# CAN_TOF.net
KiCad netlist of a schematic drawn in EAGLE
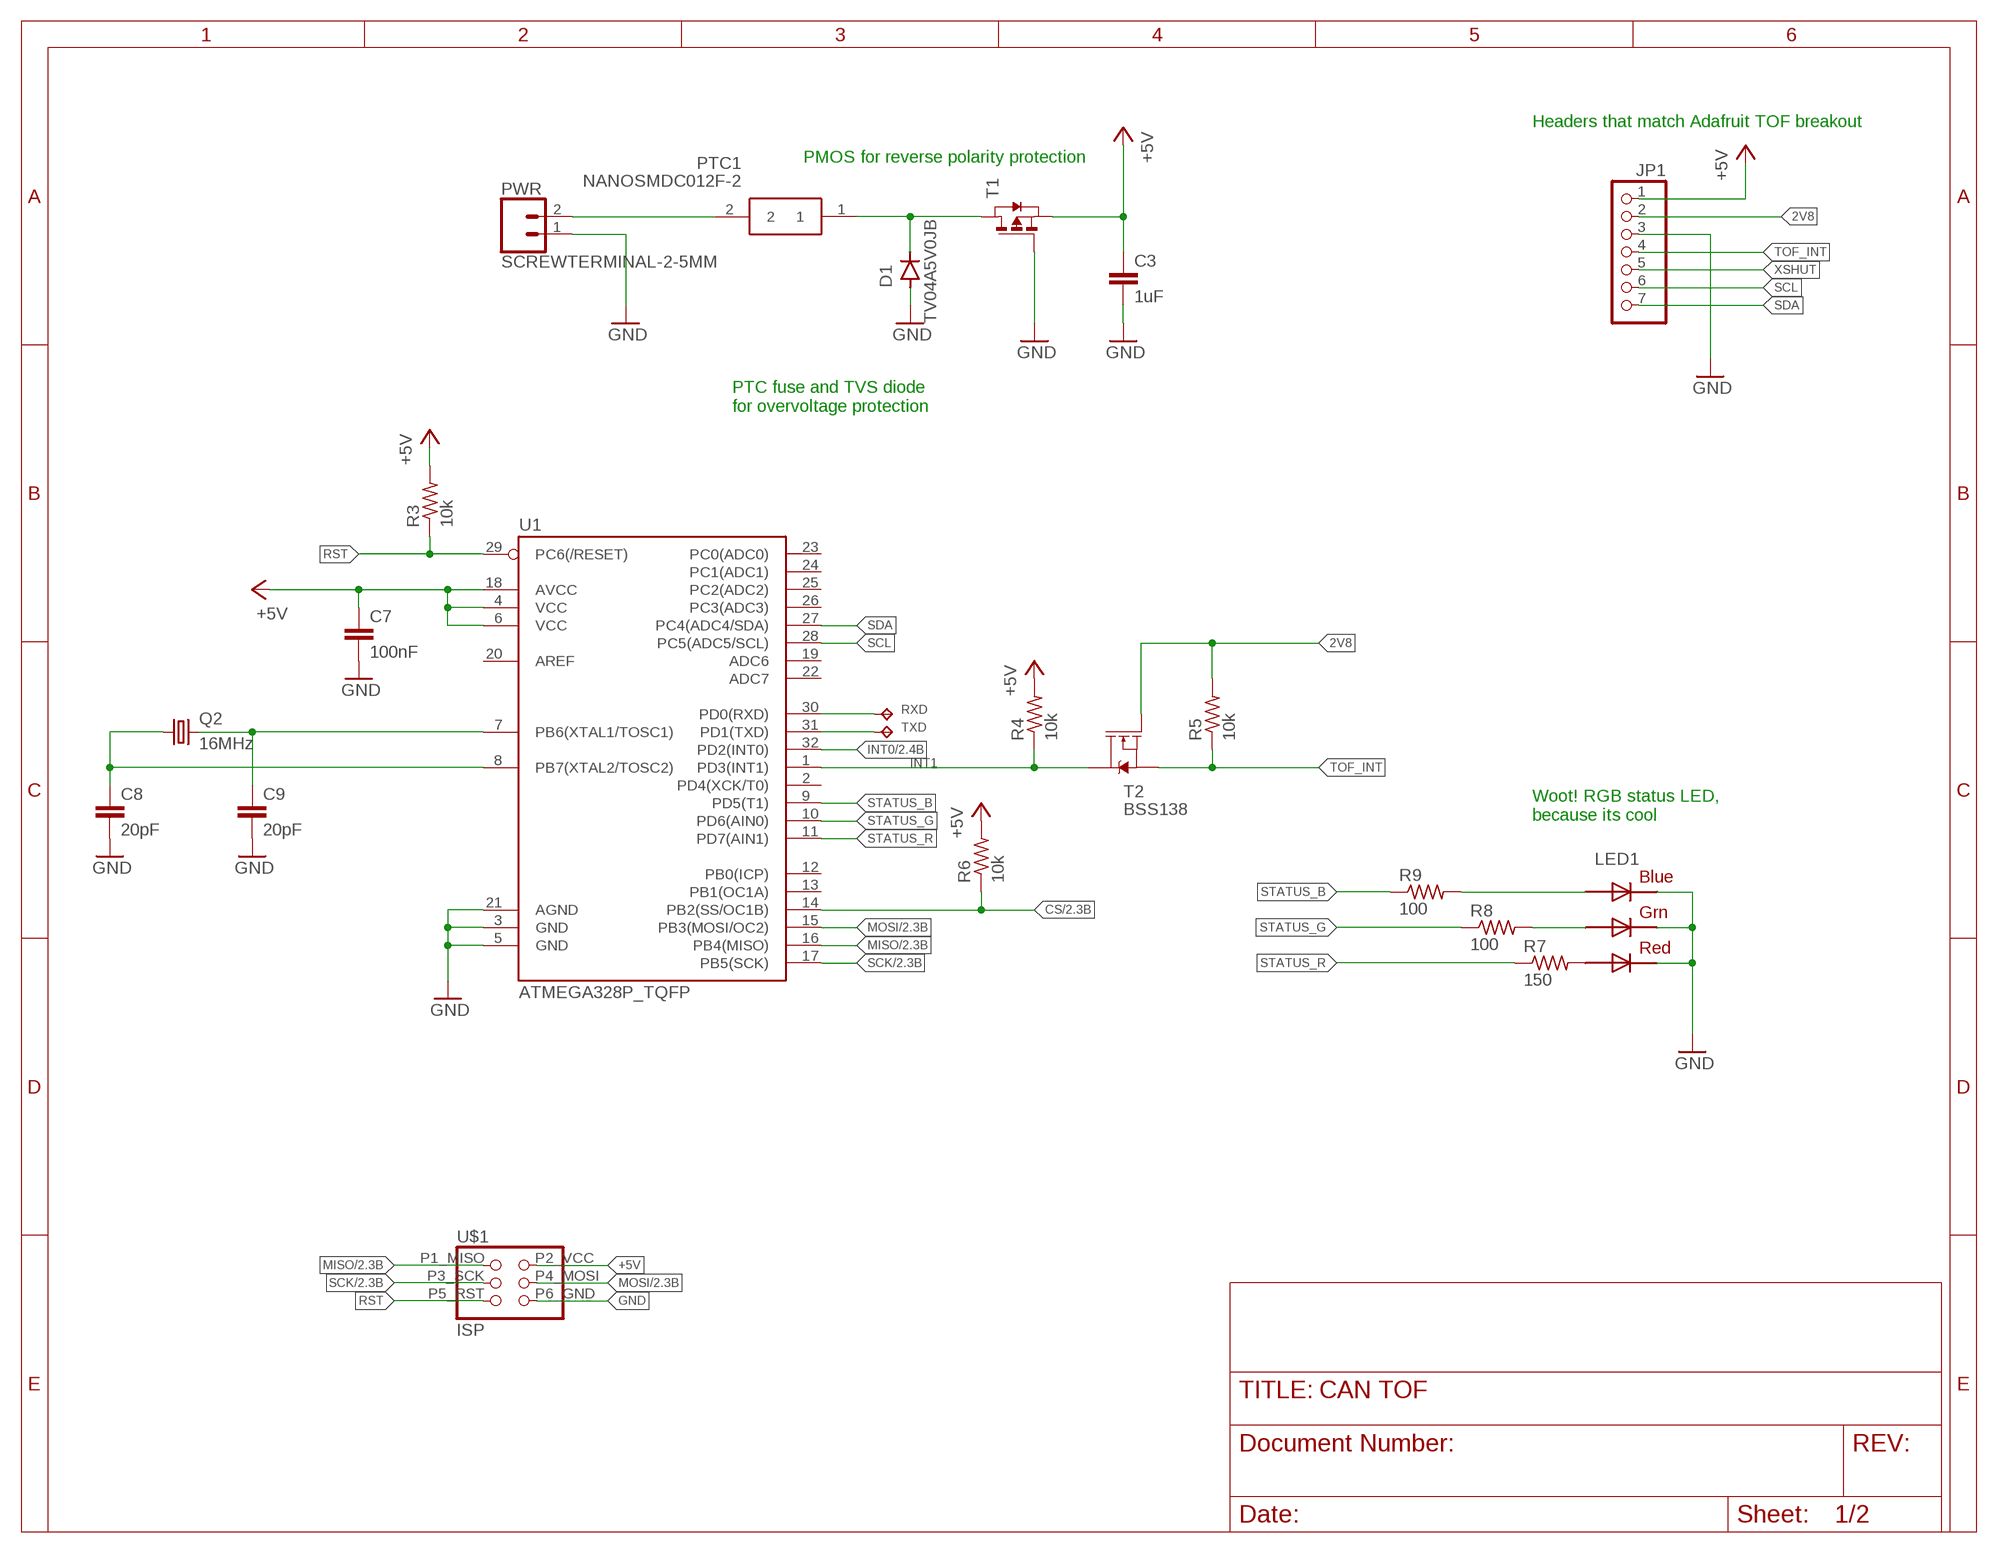
[diagram p0: schematic, sheet 1]
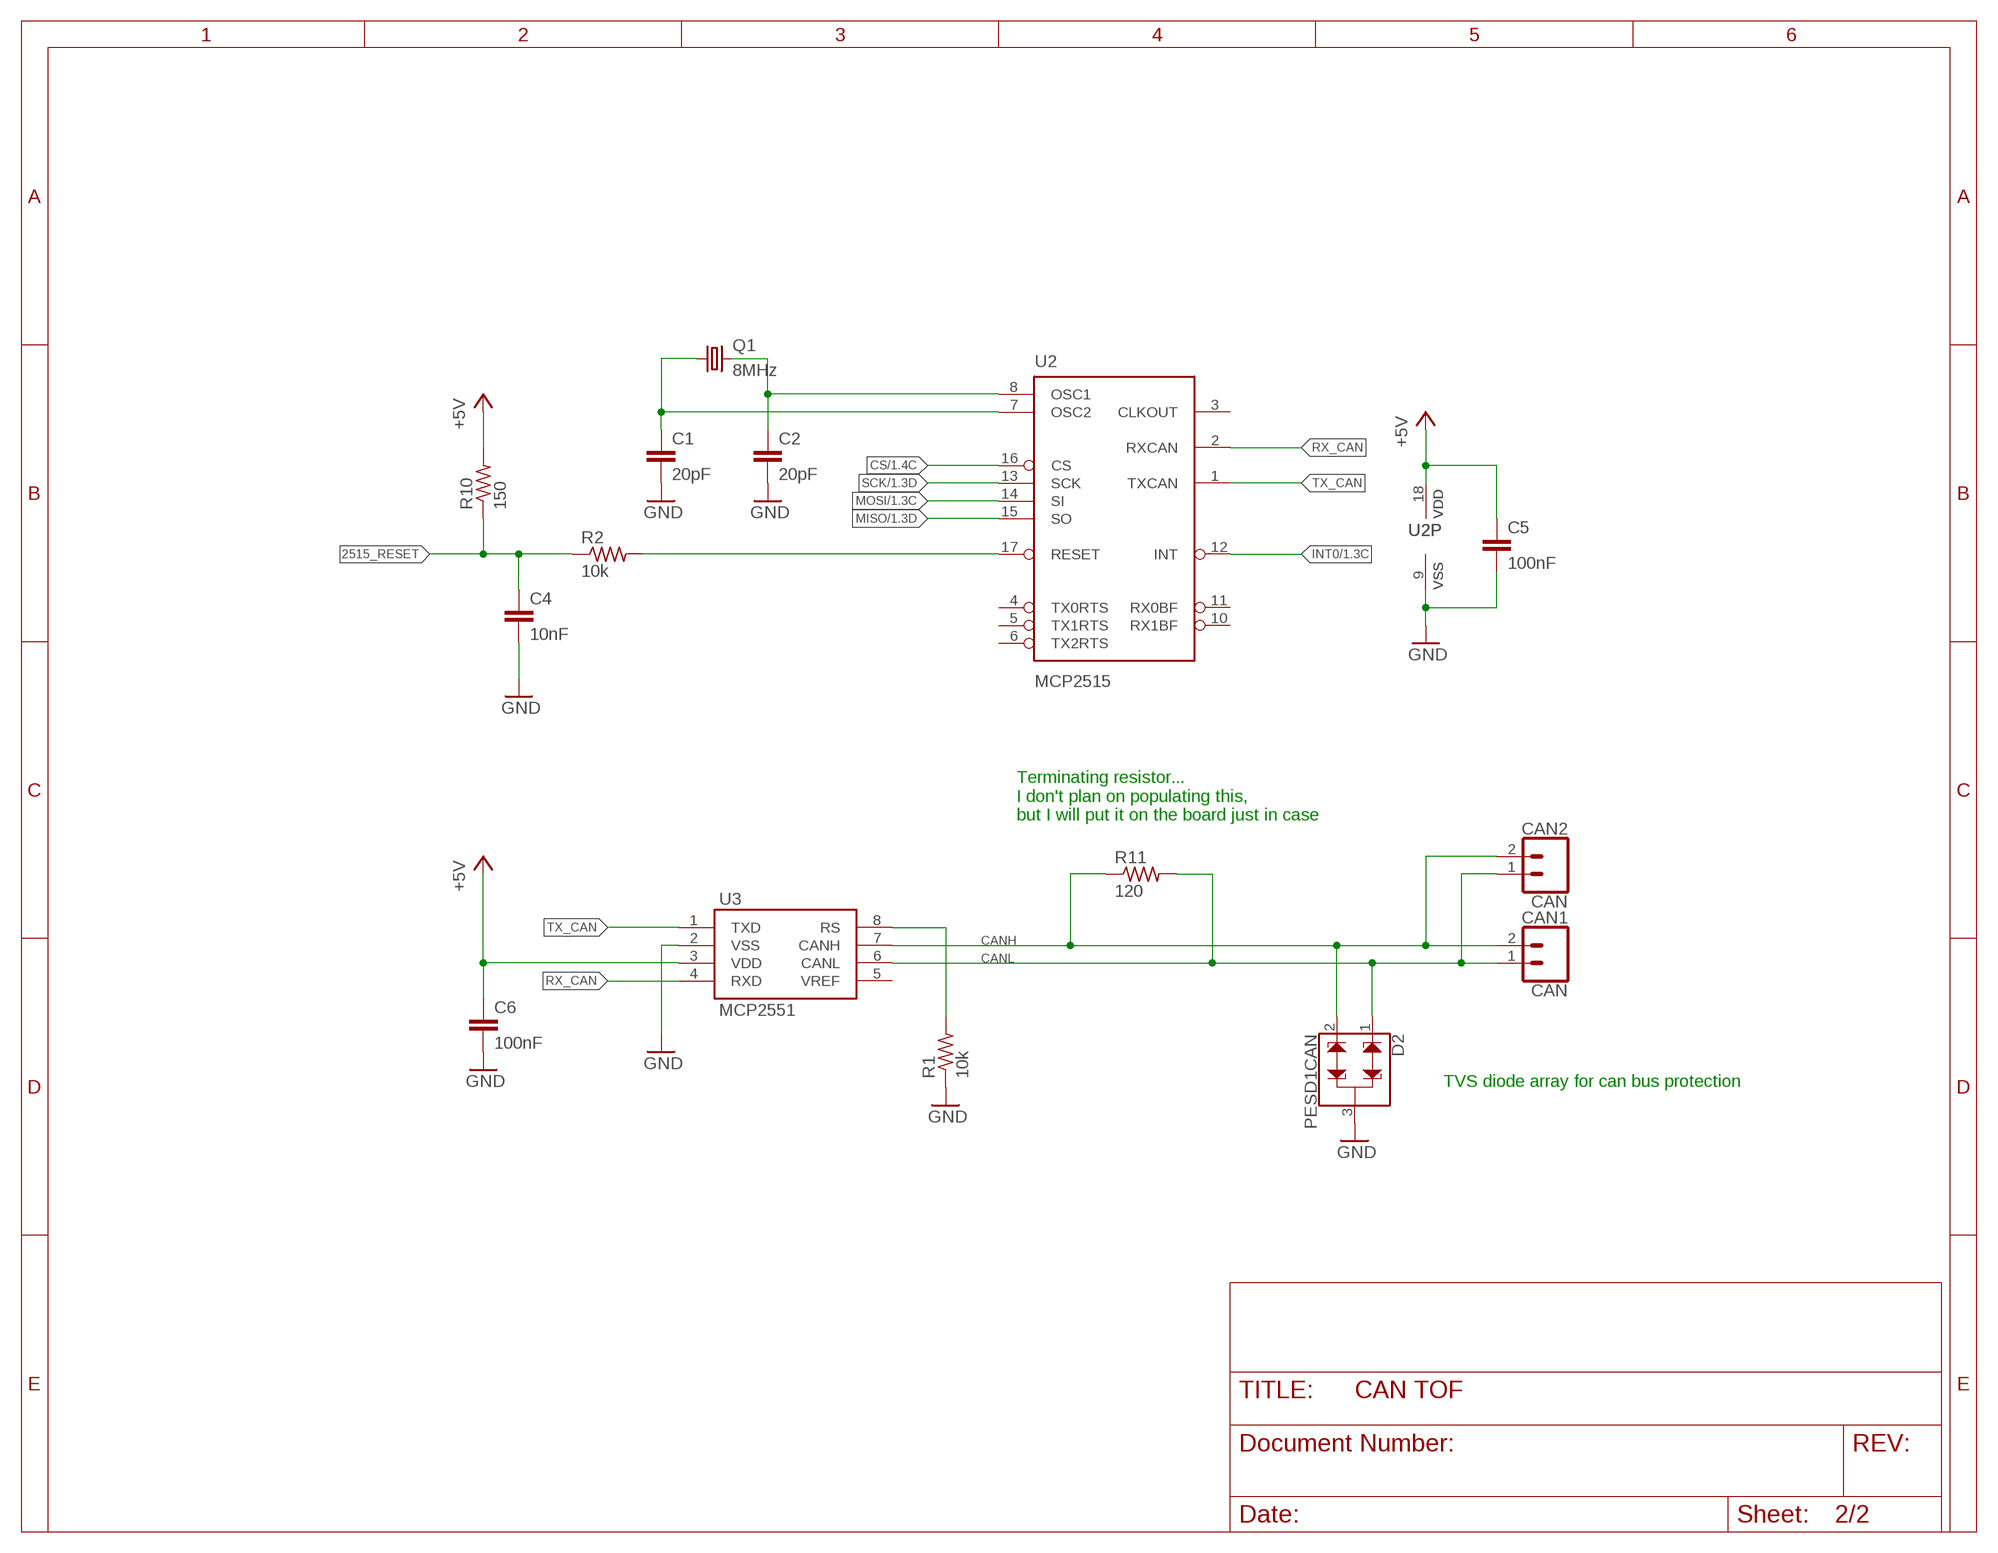
[diagram p1: schematic, sheet 2]

(export (version "E")
  (design (tool "Eeschema 10.0.6"))
  (components
    (comp (ref "C3")
      (value "1uF")
      (footprint "eagle-import:C0805")
      (libsource (lib "eagle-import") (part "C-EUC0805"))
    )
    (comp (ref "C7")
      (value "100nF")
      (footprint "eagle-import:C0402")
      (libsource (lib "eagle-import") (part "C-EUC0402"))
    )
    (comp (ref "C8")
      (value "20pF")
      (footprint "eagle-import:C0402")
      (libsource (lib "eagle-import") (part "C-EUC0402"))
    )
    (comp (ref "C9")
      (value "20pF")
      (footprint "eagle-import:C0402")
      (libsource (lib "eagle-import") (part "C-EUC0402"))
    )
    (comp (ref "D1")
      (value "TV04A5V0JB")
      (footprint "eagle-import:SMA-DO214AC")
      (libsource (lib "eagle-import") (part "GF1"))
    )
    (comp (ref "JP1")
      (value "PINHD-1X7")
      (footprint "eagle-import:1X07")
      (libsource (lib "eagle-import") (part "PINHD-1X7"))
    )
    (comp (ref "LED1")
      (value "RGBLED5050")
      (footprint "eagle-import:RGBLED5050")
      (libsource (lib "eagle-import") (part "RGBLED5050"))
    )
    (comp (ref "PTC1")
      (value "NANOSMDC012F-2")
      (footprint "eagle-import:FUSC3216X100N")
      (fields
        (field (name "MANUFACTURER_PART_NUMBER") "NANOSMDC010F-2")
        (field (name "MOUSER_PART_NUMBER") "650-NANOSMDC010F-2")
      )
      (libsource (lib "eagle-import") (part "NANOSMDC010F-2"))
    )
    (comp (ref "PWR")
      (value "SCREWTERMINAL-2-5MM")
      (footprint "eagle-import:SCREWTERMINAL-5MM-2")
      (libsource (lib "eagle-import") (part "SCREWTERMINAL-2-5MM"))
    )
    (comp (ref "Q2")
      (value "16MHz")
      (footprint "eagle-import:CTS406")
      (libsource (lib "eagle-import") (part "CRYSTALCTS406"))
    )
    (comp (ref "R3")
      (value "10k")
      (footprint "eagle-import:R0805")
      (libsource (lib "eagle-import") (part "R-US_R0805"))
    )
    (comp (ref "R4")
      (value "10k")
      (footprint "eagle-import:R0805")
      (libsource (lib "eagle-import") (part "R-US_R0805"))
    )
    (comp (ref "R5")
      (value "10k")
      (footprint "eagle-import:R0805")
      (libsource (lib "eagle-import") (part "R-US_R0805"))
    )
    (comp (ref "R6")
      (value "10k")
      (footprint "eagle-import:R0805")
      (libsource (lib "eagle-import") (part "R-US_R0805"))
    )
    (comp (ref "R7")
      (value "150")
      (footprint "eagle-import:R0805")
      (libsource (lib "eagle-import") (part "R-US_R0805"))
    )
    (comp (ref "R8")
      (value "100")
      (footprint "eagle-import:R0805")
      (libsource (lib "eagle-import") (part "R-US_R0805"))
    )
    (comp (ref "R9")
      (value "100")
      (footprint "eagle-import:R0805")
      (libsource (lib "eagle-import") (part "R-US_R0805"))
    )
    (comp (ref "RXD")
      (value "TPB1,27")
      (footprint "eagle-import:B1,27")
      (libsource (lib "eagle-import") (part "TPB1,27"))
    )
    (comp (ref "T1")
      (value "PMOSSOT23")
      (footprint "eagle-import:SOT-23")
      (libsource (lib "eagle-import") (part "PMOSSOT23"))
    )
    (comp (ref "T2")
      (value "BSS138")
      (footprint "eagle-import:SOT23-3")
      (libsource (lib "eagle-import") (part "MOSFET-NCH-BSS138"))
    )
    (comp (ref "TXD")
      (value "TPB1,27")
      (footprint "eagle-import:B1,27")
      (libsource (lib "eagle-import") (part "TPB1,27"))
    )
    (comp (ref "U$1")
      (value "ISP")
      (footprint "eagle-import:ISP")
      (libsource (lib "eagle-import") (part "ISP"))
    )
    (comp (ref "U1")
      (value "ATMEGA328P_TQFP")
      (footprint "eagle-import:TQFP32-08")
      (libsource (lib "eagle-import") (part "ATMEGA328P_TQFP"))
    )
    (comp (ref "C1")
      (value "20pF")
      (footprint "eagle-import:C0402")
      (libsource (lib "eagle-import") (part "C-EUC0402"))
    )
    (comp (ref "C2")
      (value "20pF")
      (footprint "eagle-import:C0402")
      (libsource (lib "eagle-import") (part "C-EUC0402"))
    )
    (comp (ref "C4")
      (value "10nF")
      (footprint "eagle-import:C0402")
      (libsource (lib "eagle-import") (part "C-EUC0402"))
    )
    (comp (ref "C5")
      (value "100nF")
      (footprint "eagle-import:C0402")
      (libsource (lib "eagle-import") (part "C-EUC0402"))
    )
    (comp (ref "C6")
      (value "100nF")
      (footprint "eagle-import:C0402")
      (libsource (lib "eagle-import") (part "C-EUC0402"))
    )
    (comp (ref "CAN1")
      (value "CAN")
      (footprint "eagle-import:SCREWTERMINAL-5MM-2")
      (libsource (lib "eagle-import") (part "SCREWTERMINAL-2-5MM"))
    )
    (comp (ref "CAN2")
      (value "CAN")
      (footprint "eagle-import:SCREWTERMINAL-5MM-2")
      (libsource (lib "eagle-import") (part "SCREWTERMINAL-2-5MM"))
    )
    (comp (ref "D2")
      (value "PESD1CAN")
      (footprint "eagle-import:SOT23-3")
      (libsource (lib "eagle-import") (part "PESD1CAN"))
    )
    (comp (ref "Q1")
      (value "8MHz")
      (footprint "eagle-import:CTS406")
      (libsource (lib "eagle-import") (part "CRYSTALCTS406"))
    )
    (comp (ref "R1")
      (value "10k")
      (footprint "eagle-import:R0805")
      (libsource (lib "eagle-import") (part "R-US_R0805"))
    )
    (comp (ref "R2")
      (value "10k")
      (footprint "eagle-import:R0805")
      (libsource (lib "eagle-import") (part "R-US_R0805"))
    )
    (comp (ref "R10")
      (value "150")
      (footprint "eagle-import:R0805")
      (libsource (lib "eagle-import") (part "R-US_R0805"))
    )
    (comp (ref "R11")
      (value "120")
      (footprint "eagle-import:R0805")
      (libsource (lib "eagle-import") (part "R-US_R0805"))
    )
    (comp (ref "U2")
      (value "MCP2515")
      (footprint "eagle-import:SO18W")
      (libsource (lib "eagle-import") (part "MCP2515(MCP2510)SO"))
    )
    (comp (ref "U3")
      (value "MCP2551")
      (footprint "eagle-import:SO08")
      (libsource (lib "eagle-import") (part "MCP2551"))
    )
  )
  (nets
    (net (code "1") (name "+5V") (class "Default")
      (node (ref "C3") (pin "1") (pinfunction "1_1") (pintype "passive"))
      (node (ref "C5") (pin "1") (pinfunction "1_1") (pintype "passive"))
      (node (ref "C6") (pin "1") (pinfunction "1_1") (pintype "passive"))
      (node (ref "C7") (pin "1") (pinfunction "1_1") (pintype "passive"))
      (node (ref "JP1") (pin "1") (pinfunction "1_1") (pintype "passive"))
      (node (ref "R10") (pin "2") (pinfunction "2_2") (pintype "passive"))
      (node (ref "R3") (pin "2") (pinfunction "2_2") (pintype "passive"))
      (node (ref "R4") (pin "2") (pinfunction "2_2") (pintype "passive"))
      (node (ref "R6") (pin "2") (pinfunction "2_2") (pintype "passive"))
      (node (ref "T1") (pin "2") (pinfunction "S_2") (pintype "passive"))
      (node (ref "U$1") (pin "P2_VCC") (pinfunction "VCC_P2_VCC") (pintype "passive"))
      (node (ref "U1") (pin "18") (pinfunction "AVCC_18") (pintype "bidirectional"))
      (node (ref "U1") (pin "4") (pinfunction "VCC_4") (pintype "bidirectional"))
      (node (ref "U1") (pin "6") (pinfunction "VCC_6") (pintype "bidirectional"))
      (node (ref "U2") (pin "18") (pinfunction "VDD_18") (pintype "power_in"))
      (node (ref "U3") (pin "3") (pinfunction "VDD_3") (pintype "bidirectional"))
    )
    (net (code "2") (name "2V8") (class "Default")
      (node (ref "JP1") (pin "2") (pinfunction "2_2") (pintype "passive"))
      (node (ref "R5") (pin "2") (pinfunction "2_2") (pintype "passive"))
      (node (ref "T2") (pin "1") (pinfunction "G_1") (pintype "bidirectional"))
    )
    (net (code "3") (name "2515_RESET") (class "Default")
      (node (ref "C4") (pin "1") (pinfunction "1_1") (pintype "passive"))
      (node (ref "R10") (pin "1") (pinfunction "1_1") (pintype "passive"))
      (node (ref "R2") (pin "1") (pinfunction "1_1") (pintype "passive"))
    )
    (net (code "4") (name "CANH") (class "Default")
      (node (ref "CAN1") (pin "2") (pinfunction "2_2") (pintype "passive"))
      (node (ref "CAN2") (pin "2") (pinfunction "2_2") (pintype "passive"))
      (node (ref "D2") (pin "2") (pinfunction "2_2") (pintype "bidirectional"))
      (node (ref "R11") (pin "1") (pinfunction "1_1") (pintype "passive"))
      (node (ref "U3") (pin "7") (pinfunction "CANH_7") (pintype "bidirectional"))
    )
    (net (code "5") (name "CANL") (class "Default")
      (node (ref "CAN1") (pin "1") (pinfunction "1_1") (pintype "passive"))
      (node (ref "CAN2") (pin "1") (pinfunction "1_1") (pintype "passive"))
      (node (ref "D2") (pin "1") (pinfunction "1_1") (pintype "bidirectional"))
      (node (ref "R11") (pin "2") (pinfunction "2_2") (pintype "passive"))
      (node (ref "U3") (pin "6") (pinfunction "CANL_6") (pintype "bidirectional"))
    )
    (net (code "6") (name "CS") (class "Default")
      (node (ref "R6") (pin "1") (pinfunction "1_1") (pintype "passive"))
      (node (ref "U1") (pin "14") (pinfunction "PB2(SS/OC1B)_14") (pintype "bidirectional"))
      (node (ref "U2") (pin "16") (pinfunction "CS_16") (pintype "input"))
    )
    (net (code "7") (name "GND") (class "Default")
      (node (ref "C1") (pin "2") (pinfunction "2_2") (pintype "passive"))
      (node (ref "C2") (pin "2") (pinfunction "2_2") (pintype "passive"))
      (node (ref "C3") (pin "2") (pinfunction "2_2") (pintype "passive"))
      (node (ref "C4") (pin "2") (pinfunction "2_2") (pintype "passive"))
      (node (ref "C5") (pin "2") (pinfunction "2_2") (pintype "passive"))
      (node (ref "C6") (pin "2") (pinfunction "2_2") (pintype "passive"))
      (node (ref "C7") (pin "2") (pinfunction "2_2") (pintype "passive"))
      (node (ref "C8") (pin "2") (pinfunction "2_2") (pintype "passive"))
      (node (ref "C9") (pin "2") (pinfunction "2_2") (pintype "passive"))
      (node (ref "D1") (pin "A") (pinfunction "A_A") (pintype "passive"))
      (node (ref "D2") (pin "3") (pinfunction "3_3") (pintype "bidirectional"))
      (node (ref "JP1") (pin "3") (pinfunction "3_3") (pintype "passive"))
      (node (ref "LED1") (pin "4") (pinfunction "BLUE_C_4") (pintype "bidirectional"))
      (node (ref "LED1") (pin "5") (pinfunction "RED_C_5") (pintype "bidirectional"))
      (node (ref "LED1") (pin "6") (pinfunction "GREEN_C_6") (pintype "bidirectional"))
      (node (ref "PWR") (pin "1") (pinfunction "1_1") (pintype "passive"))
      (node (ref "R1") (pin "1") (pinfunction "1_1") (pintype "passive"))
      (node (ref "T1") (pin "3") (pinfunction "G_3") (pintype "passive"))
      (node (ref "U$1") (pin "P6_GND") (pinfunction "GND_P6_GND") (pintype "passive"))
      (node (ref "U1") (pin "21") (pinfunction "AGND_21") (pintype "bidirectional"))
      (node (ref "U1") (pin "3") (pinfunction "GND_3") (pintype "bidirectional"))
      (node (ref "U1") (pin "5") (pinfunction "GND_5") (pintype "bidirectional"))
      (node (ref "U2") (pin "9") (pinfunction "VSS_9") (pintype "power_in"))
      (node (ref "U3") (pin "2") (pinfunction "VSS_2") (pintype "bidirectional"))
    )
    (net (code "8") (name "INT0") (class "Default")
      (node (ref "U1") (pin "32") (pinfunction "PD2(INT0)_32") (pintype "bidirectional"))
      (node (ref "U2") (pin "12") (pinfunction "INT_12") (pintype "output"))
    )
    (net (code "9") (name "INT1") (class "Default")
      (node (ref "R4") (pin "1") (pinfunction "1_1") (pintype "passive"))
      (node (ref "T2") (pin "3") (pinfunction "D_3") (pintype "bidirectional"))
      (node (ref "U1") (pin "1") (pinfunction "PD3(INT1)_1") (pintype "bidirectional"))
    )
    (net (code "10") (name "MISO") (class "Default")
      (node (ref "U$1") (pin "P1_MISO") (pinfunction "MISO_P1_MISO") (pintype "passive"))
      (node (ref "U1") (pin "16") (pinfunction "PB4(MISO)_16") (pintype "bidirectional"))
      (node (ref "U2") (pin "15") (pinfunction "SO_15") (pintype "output"))
    )
    (net (code "11") (name "MOSI") (class "Default")
      (node (ref "U$1") (pin "P4_MOSI") (pinfunction "MOSI_P4_MOSI") (pintype "passive"))
      (node (ref "U1") (pin "15") (pinfunction "PB3(MOSI/OC2)_15") (pintype "bidirectional"))
      (node (ref "U2") (pin "14") (pinfunction "SI_14") (pintype "input"))
    )
    (net (code "12") (name "Net-(D1-C)") (class "Default")
      (node (ref "D1") (pin "K") (pinfunction "C_K") (pintype "passive"))
      (node (ref "PTC1") (pin "1") (pinfunction "1_1") (pintype "bidirectional"))
      (node (ref "T1") (pin "1") (pinfunction "D_1") (pintype "passive"))
    )
    (net (code "13") (name "Net-(LED1-BLUE_A)") (class "Default")
      (node (ref "LED1") (pin "3") (pinfunction "BLUE_A_3") (pintype "bidirectional"))
      (node (ref "R9") (pin "2") (pinfunction "2_2") (pintype "passive"))
    )
    (net (code "14") (name "Net-(LED1-GREEN_A)") (class "Default")
      (node (ref "LED1") (pin "1") (pinfunction "GREEN_A_1") (pintype "bidirectional"))
      (node (ref "R8") (pin "2") (pinfunction "2_2") (pintype "passive"))
    )
    (net (code "15") (name "Net-(LED1-RED_A)") (class "Default")
      (node (ref "LED1") (pin "2") (pinfunction "RED_A_2") (pintype "bidirectional"))
      (node (ref "R7") (pin "2") (pinfunction "2_2") (pintype "passive"))
    )
    (net (code "16") (name "Net-(PTC1-Pad2)") (class "Default")
      (node (ref "PTC1") (pin "2") (pinfunction "2_2") (pintype "bidirectional"))
      (node (ref "PWR") (pin "2") (pinfunction "2_2") (pintype "passive"))
    )
    (net (code "17") (name "Net-(Q1-2)") (class "Default")
      (node (ref "C2") (pin "1") (pinfunction "1_1") (pintype "passive"))
      (node (ref "Q1") (pin "3") (pinfunction "2_3") (pintype "passive"))
      (node (ref "U2") (pin "8") (pinfunction "OSC1_8") (pintype "input"))
    )
    (net (code "18") (name "Net-(Q2-2)") (class "Default")
      (node (ref "C9") (pin "1") (pinfunction "1_1") (pintype "passive"))
      (node (ref "Q2") (pin "3") (pinfunction "2_3") (pintype "passive"))
      (node (ref "U1") (pin "7") (pinfunction "PB6(XTAL1/TOSC1)_7") (pintype "bidirectional"))
    )
    (net (code "19") (name "Net-(U1-PB7(XTAL2{slash}TOSC2))") (class "Default")
      (node (ref "C8") (pin "1") (pinfunction "1_1") (pintype "passive"))
      (node (ref "Q2") (pin "1") (pinfunction "1_1") (pintype "passive"))
      (node (ref "U1") (pin "8") (pinfunction "PB7(XTAL2/TOSC2)_8") (pintype "bidirectional"))
    )
    (net (code "20") (name "Net-(U1-PD0(RXD))") (class "Default")
      (node (ref "RXD") (pin "TP") (pinfunction "TP_TP") (pintype "input"))
      (node (ref "U1") (pin "30") (pinfunction "PD0(RXD)_30") (pintype "bidirectional"))
    )
    (net (code "21") (name "Net-(U1-PD1(TXD))") (class "Default")
      (node (ref "TXD") (pin "TP") (pinfunction "TP_TP") (pintype "input"))
      (node (ref "U1") (pin "31") (pinfunction "PD1(TXD)_31") (pintype "bidirectional"))
    )
    (net (code "22") (name "Net-(U2A-OSC2)") (class "Default")
      (node (ref "C1") (pin "1") (pinfunction "1_1") (pintype "passive"))
      (node (ref "Q1") (pin "1") (pinfunction "1_1") (pintype "passive"))
      (node (ref "U2") (pin "7") (pinfunction "OSC2_7") (pintype "output"))
    )
    (net (code "23") (name "Net-(U2A-RESET)") (class "Default")
      (node (ref "R2") (pin "2") (pinfunction "2_2") (pintype "passive"))
      (node (ref "U2") (pin "17") (pinfunction "RESET_17") (pintype "input"))
    )
    (net (code "24") (name "Net-(U3-RS)") (class "Default")
      (node (ref "R1") (pin "2") (pinfunction "2_2") (pintype "passive"))
      (node (ref "U3") (pin "8") (pinfunction "RS_8") (pintype "bidirectional"))
    )
    (net (code "25") (name "RST") (class "Default")
      (node (ref "R3") (pin "1") (pinfunction "1_1") (pintype "passive"))
      (node (ref "U$1") (pin "P5_RST") (pinfunction "RST_P5_RST") (pintype "passive"))
      (node (ref "U1") (pin "29") (pinfunction "PC6(/RESET)_29") (pintype "bidirectional"))
    )
    (net (code "26") (name "RX_CAN") (class "Default")
      (node (ref "U2") (pin "2") (pinfunction "RXCAN_2") (pintype "input"))
      (node (ref "U3") (pin "4") (pinfunction "RXD_4") (pintype "bidirectional"))
    )
    (net (code "27") (name "SCK") (class "Default")
      (node (ref "U$1") (pin "P3_SCK") (pinfunction "SCK_P3_SCK") (pintype "passive"))
      (node (ref "U1") (pin "17") (pinfunction "PB5(SCK)_17") (pintype "bidirectional"))
      (node (ref "U2") (pin "13") (pinfunction "SCK_13") (pintype "input"))
    )
    (net (code "28") (name "SCL") (class "Default")
      (node (ref "JP1") (pin "6") (pinfunction "6_6") (pintype "passive"))
      (node (ref "U1") (pin "28") (pinfunction "PC5(ADC5/SCL)_28") (pintype "bidirectional"))
    )
    (net (code "29") (name "SDA") (class "Default")
      (node (ref "JP1") (pin "7") (pinfunction "7_7") (pintype "passive"))
      (node (ref "U1") (pin "27") (pinfunction "PC4(ADC4/SDA)_27") (pintype "bidirectional"))
    )
    (net (code "30") (name "STATUS_B") (class "Default")
      (node (ref "R9") (pin "1") (pinfunction "1_1") (pintype "passive"))
      (node (ref "U1") (pin "9") (pinfunction "PD5(T1)_9") (pintype "bidirectional"))
    )
    (net (code "31") (name "STATUS_G") (class "Default")
      (node (ref "R8") (pin "1") (pinfunction "1_1") (pintype "passive"))
      (node (ref "U1") (pin "10") (pinfunction "PD6(AIN0)_10") (pintype "bidirectional"))
    )
    (net (code "32") (name "STATUS_R") (class "Default")
      (node (ref "R7") (pin "1") (pinfunction "1_1") (pintype "passive"))
      (node (ref "U1") (pin "11") (pinfunction "PD7(AIN1)_11") (pintype "bidirectional"))
    )
    (net (code "33") (name "TOF_INT") (class "Default")
      (node (ref "JP1") (pin "4") (pinfunction "4_4") (pintype "passive"))
      (node (ref "R5") (pin "1") (pinfunction "1_1") (pintype "passive"))
      (node (ref "T2") (pin "2") (pinfunction "S_2") (pintype "bidirectional"))
    )
    (net (code "34") (name "TX_CAN") (class "Default")
      (node (ref "U2") (pin "1") (pinfunction "TXCAN_1") (pintype "output"))
      (node (ref "U3") (pin "1") (pinfunction "TXD_1") (pintype "bidirectional"))
    )
    (net (code "35") (name "XSHUT") (class "Default")
      (node (ref "JP1") (pin "5") (pinfunction "5_5") (pintype "passive"))
    )
    (net (code "36") (name "unconnected-(U1-ADC6-Pad19)") (class "Default")
      (node (ref "U1") (pin "19") (pinfunction "ADC6_19") (pintype "bidirectional"))
    )
    (net (code "37") (name "unconnected-(U1-ADC7-Pad22)") (class "Default")
      (node (ref "U1") (pin "22") (pinfunction "ADC7_22") (pintype "bidirectional"))
    )
    (net (code "38") (name "unconnected-(U1-AREF-Pad20)") (class "Default")
      (node (ref "U1") (pin "20") (pinfunction "AREF_20") (pintype "bidirectional"))
    )
    (net (code "39") (name "unconnected-(U1-PB0(ICP)-Pad12)") (class "Default")
      (node (ref "U1") (pin "12") (pinfunction "PB0(ICP)_12") (pintype "bidirectional"))
    )
    (net (code "40") (name "unconnected-(U1-PB1(OC1A)-Pad13)") (class "Default")
      (node (ref "U1") (pin "13") (pinfunction "PB1(OC1A)_13") (pintype "bidirectional"))
    )
    (net (code "41") (name "unconnected-(U1-PC0(ADC0)-Pad23)") (class "Default")
      (node (ref "U1") (pin "23") (pinfunction "PC0(ADC0)_23") (pintype "bidirectional"))
    )
    (net (code "42") (name "unconnected-(U1-PC1(ADC1)-Pad24)") (class "Default")
      (node (ref "U1") (pin "24") (pinfunction "PC1(ADC1)_24") (pintype "bidirectional"))
    )
    (net (code "43") (name "unconnected-(U1-PC2(ADC2)-Pad25)") (class "Default")
      (node (ref "U1") (pin "25") (pinfunction "PC2(ADC2)_25") (pintype "bidirectional"))
    )
    (net (code "44") (name "unconnected-(U1-PC3(ADC3)-Pad26)") (class "Default")
      (node (ref "U1") (pin "26") (pinfunction "PC3(ADC3)_26") (pintype "bidirectional"))
    )
    (net (code "45") (name "unconnected-(U1-PD4(XCK{slash}T0)-Pad2)") (class "Default")
      (node (ref "U1") (pin "2") (pinfunction "PD4(XCK/T0)_2") (pintype "bidirectional"))
    )
    (net (code "46") (name "unconnected-(U2A-CLKOUT-Pad3)") (class "Default")
      (node (ref "U2") (pin "3") (pinfunction "CLKOUT_3") (pintype "output"))
    )
    (net (code "47") (name "unconnected-(U2A-RX0BF-Pad11)") (class "Default")
      (node (ref "U2") (pin "11") (pinfunction "RX0BF_11") (pintype "output"))
    )
    (net (code "48") (name "unconnected-(U2A-RX1BF-Pad10)") (class "Default")
      (node (ref "U2") (pin "10") (pinfunction "RX1BF_10") (pintype "output"))
    )
    (net (code "49") (name "unconnected-(U2A-TX0RTS-Pad4)") (class "Default")
      (node (ref "U2") (pin "4") (pinfunction "TX0RTS_4") (pintype "input"))
    )
    (net (code "50") (name "unconnected-(U2A-TX1RTS-Pad5)") (class "Default")
      (node (ref "U2") (pin "5") (pinfunction "TX1RTS_5") (pintype "input"))
    )
    (net (code "51") (name "unconnected-(U2A-TX2RTS-Pad6)") (class "Default")
      (node (ref "U2") (pin "6") (pinfunction "TX2RTS_6") (pintype "input"))
    )
    (net (code "52") (name "unconnected-(U3-VREF-Pad5)") (class "Default")
      (node (ref "U3") (pin "5") (pinfunction "VREF_5") (pintype "bidirectional"))
    )
  )
)
